# CROSS.net
KiCad netlist of a schematic drawn in EAGLE
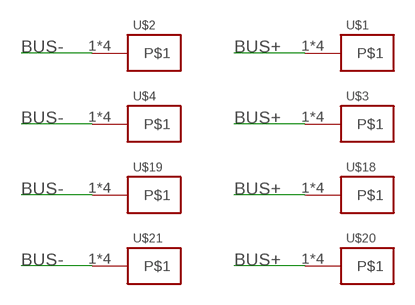
[diagram p0: schematic, sheet 1]

(export (version "E")
  (design (tool "Eeschema 10.0.6"))
  (components
    (comp (ref "U$1")
      (value "KCONNECT-")
      (footprint "eagle-import:KCONNECT-")
      (libsource (lib "eagle-import") (part "KCONNECT-"))
    )
    (comp (ref "U$2")
      (value "KCONNECT-")
      (footprint "eagle-import:KCONNECT-")
      (libsource (lib "eagle-import") (part "KCONNECT-"))
    )
    (comp (ref "U$3")
      (value "KCONNECT-")
      (footprint "eagle-import:KCONNECT-")
      (libsource (lib "eagle-import") (part "KCONNECT-"))
    )
    (comp (ref "U$4")
      (value "KCONNECT-")
      (footprint "eagle-import:KCONNECT-")
      (libsource (lib "eagle-import") (part "KCONNECT-"))
    )
    (comp (ref "U$18")
      (value "KCONNECT-")
      (footprint "eagle-import:KCONNECT-")
      (libsource (lib "eagle-import") (part "KCONNECT-"))
    )
    (comp (ref "U$19")
      (value "KCONNECT-")
      (footprint "eagle-import:KCONNECT-")
      (libsource (lib "eagle-import") (part "KCONNECT-"))
    )
    (comp (ref "U$20")
      (value "KCONNECT-")
      (footprint "eagle-import:KCONNECT-")
      (libsource (lib "eagle-import") (part "KCONNECT-"))
    )
    (comp (ref "U$21")
      (value "KCONNECT-")
      (footprint "eagle-import:KCONNECT-")
      (libsource (lib "eagle-import") (part "KCONNECT-"))
    )
  )
  (nets
    (net (code "1") (name "/BUS+") (class "Default")
      (node (ref "U$1") (pin "1") (pinfunction "P$1_1") (pintype "bidirectional"))
      (node (ref "U$1") (pin "2") (pinfunction "P$1_2") (pintype "bidirectional"))
      (node (ref "U$1") (pin "3") (pinfunction "P$1_3") (pintype "bidirectional"))
      (node (ref "U$1") (pin "4") (pinfunction "P$1_4") (pintype "bidirectional"))
      (node (ref "U$18") (pin "1") (pinfunction "P$1_1") (pintype "bidirectional"))
      (node (ref "U$18") (pin "2") (pinfunction "P$1_2") (pintype "bidirectional"))
      (node (ref "U$18") (pin "3") (pinfunction "P$1_3") (pintype "bidirectional"))
      (node (ref "U$18") (pin "4") (pinfunction "P$1_4") (pintype "bidirectional"))
      (node (ref "U$20") (pin "1") (pinfunction "P$1_1") (pintype "bidirectional"))
      (node (ref "U$20") (pin "2") (pinfunction "P$1_2") (pintype "bidirectional"))
      (node (ref "U$20") (pin "3") (pinfunction "P$1_3") (pintype "bidirectional"))
      (node (ref "U$20") (pin "4") (pinfunction "P$1_4") (pintype "bidirectional"))
      (node (ref "U$3") (pin "1") (pinfunction "P$1_1") (pintype "bidirectional"))
      (node (ref "U$3") (pin "2") (pinfunction "P$1_2") (pintype "bidirectional"))
      (node (ref "U$3") (pin "3") (pinfunction "P$1_3") (pintype "bidirectional"))
      (node (ref "U$3") (pin "4") (pinfunction "P$1_4") (pintype "bidirectional"))
    )
    (net (code "2") (name "/BUS-") (class "Default")
      (node (ref "U$19") (pin "1") (pinfunction "P$1_1") (pintype "bidirectional"))
      (node (ref "U$19") (pin "2") (pinfunction "P$1_2") (pintype "bidirectional"))
      (node (ref "U$19") (pin "3") (pinfunction "P$1_3") (pintype "bidirectional"))
      (node (ref "U$19") (pin "4") (pinfunction "P$1_4") (pintype "bidirectional"))
      (node (ref "U$2") (pin "1") (pinfunction "P$1_1") (pintype "bidirectional"))
      (node (ref "U$2") (pin "2") (pinfunction "P$1_2") (pintype "bidirectional"))
      (node (ref "U$2") (pin "3") (pinfunction "P$1_3") (pintype "bidirectional"))
      (node (ref "U$2") (pin "4") (pinfunction "P$1_4") (pintype "bidirectional"))
      (node (ref "U$21") (pin "1") (pinfunction "P$1_1") (pintype "bidirectional"))
      (node (ref "U$21") (pin "2") (pinfunction "P$1_2") (pintype "bidirectional"))
      (node (ref "U$21") (pin "3") (pinfunction "P$1_3") (pintype "bidirectional"))
      (node (ref "U$21") (pin "4") (pinfunction "P$1_4") (pintype "bidirectional"))
      (node (ref "U$4") (pin "1") (pinfunction "P$1_1") (pintype "bidirectional"))
      (node (ref "U$4") (pin "2") (pinfunction "P$1_2") (pintype "bidirectional"))
      (node (ref "U$4") (pin "3") (pinfunction "P$1_3") (pintype "bidirectional"))
      (node (ref "U$4") (pin "4") (pinfunction "P$1_4") (pintype "bidirectional"))
    )
  )
)
